# 5_SDRAM.net
KiCad netlist of a schematic drawn in Altium Designer
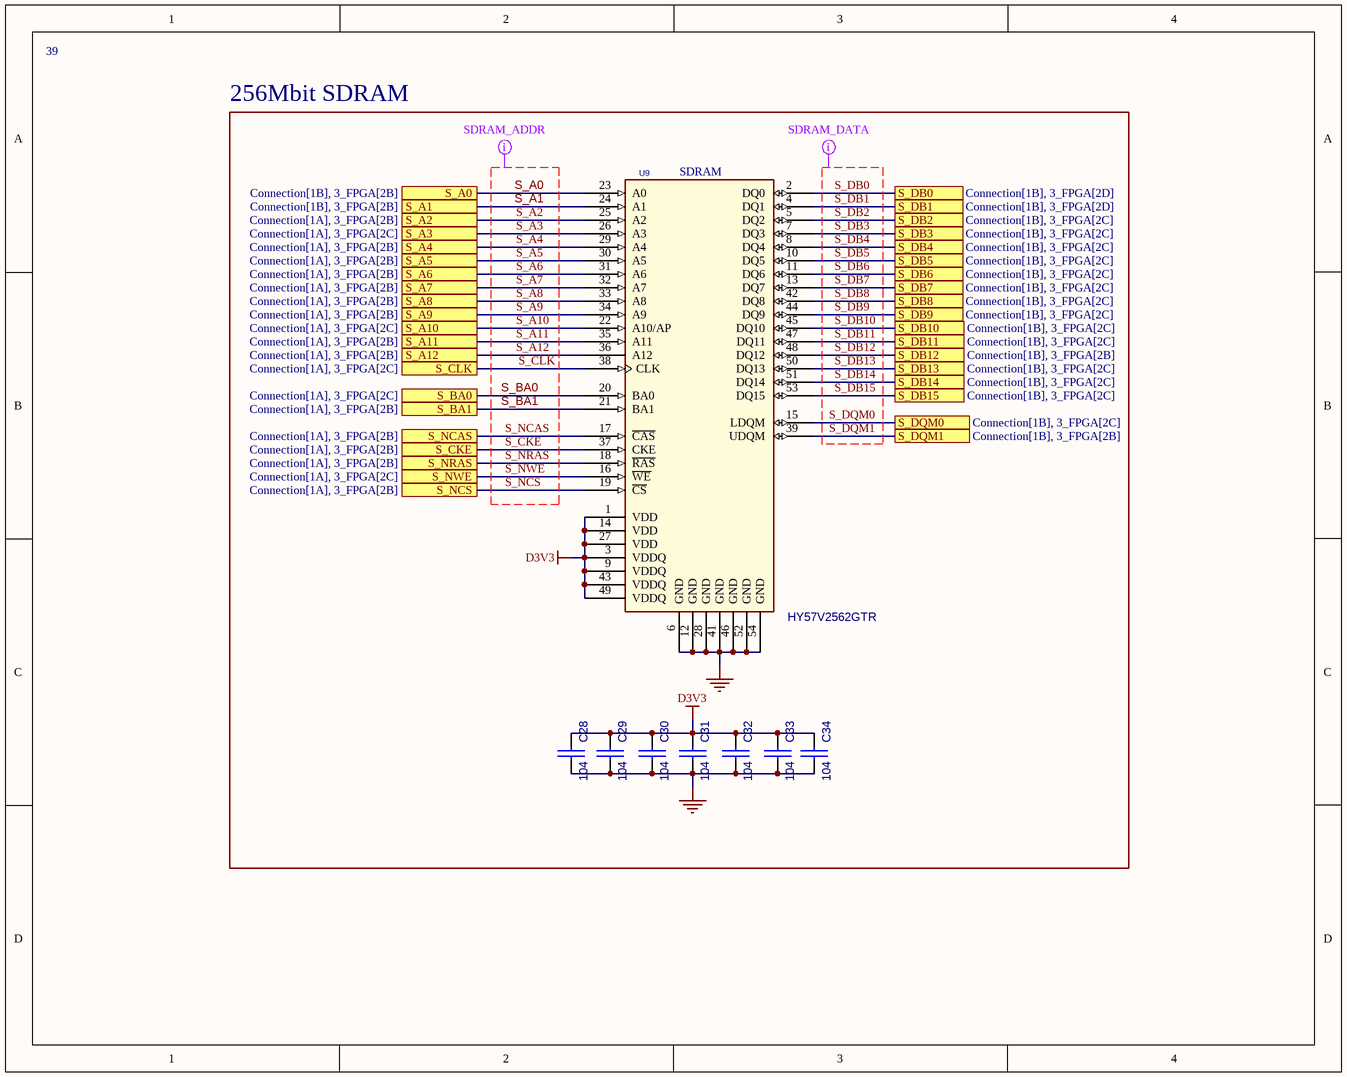
[diagram p0: 5_SDRAM.SchDoc]

(export (version "E")
  (design (tool "Eeschema 10.0.6"))
  (components
    (comp (ref "C28") (value "104") (footprint "0402 Cap") (libsource (lib "SPARTAN6") (part "C_Dup3")))
    (comp (ref "C29") (value "104") (footprint "0402 Cap") (libsource (lib "SPARTAN6") (part "C_Dup3")))
    (comp (ref "C30") (value "104") (footprint "0402 Cap") (libsource (lib "SPARTAN6") (part "C_Dup3")))
    (comp (ref "C31") (value "104") (footprint "0402 Cap") (libsource (lib "SPARTAN6") (part "C_Dup3")))
    (comp (ref "C32") (value "104") (footprint "0402 Cap") (libsource (lib "SPARTAN6") (part "C_Dup3")))
    (comp (ref "C33") (value "104") (footprint "0402 Cap") (libsource (lib "SPARTAN6") (part "C_Dup3")))
    (comp (ref "C34") (value "104") (footprint "0402 Cap") (libsource (lib "SPARTAN6") (part "C_Dup3")))
    (comp (ref "U9") (value "HY57V2562GTR") (libsource (lib "*") (part "HY57651620/SO_0")))
  )
  (nets
    (net (code "1") (name "/S_A0") (class "Default")
      (node (ref "U9") (pin "23") (pinfunction "A0_23") (pintype "input"))
    )
    (net (code "2") (name "/S_A1") (class "Default")
      (node (ref "U9") (pin "24") (pinfunction "A1_24") (pintype "input"))
    )
    (net (code "3") (name "/S_A2") (class "Default")
      (node (ref "U9") (pin "25") (pinfunction "A2_25") (pintype "input"))
    )
    (net (code "4") (name "/S_A3") (class "Default")
      (node (ref "U9") (pin "26") (pinfunction "A3_26") (pintype "input"))
    )
    (net (code "5") (name "/S_A4") (class "Default")
      (node (ref "U9") (pin "29") (pinfunction "A4_29") (pintype "input"))
    )
    (net (code "6") (name "/S_A5") (class "Default")
      (node (ref "U9") (pin "30") (pinfunction "A5_30") (pintype "input"))
    )
    (net (code "7") (name "/S_A6") (class "Default")
      (node (ref "U9") (pin "31") (pinfunction "A6_31") (pintype "input"))
    )
    (net (code "8") (name "/S_A7") (class "Default")
      (node (ref "U9") (pin "32") (pinfunction "A7_32") (pintype "input"))
    )
    (net (code "9") (name "/S_A8") (class "Default")
      (node (ref "U9") (pin "33") (pinfunction "A8_33") (pintype "input"))
    )
    (net (code "10") (name "/S_A9") (class "Default")
      (node (ref "U9") (pin "34") (pinfunction "A9_34") (pintype "input"))
    )
    (net (code "11") (name "/S_A10") (class "Default")
      (node (ref "U9") (pin "22") (pinfunction "A10/AP_22") (pintype "input"))
    )
    (net (code "12") (name "/S_A11") (class "Default")
      (node (ref "U9") (pin "35") (pinfunction "A11_35") (pintype "input"))
    )
    (net (code "13") (name "/S_A12") (class "Default")
      (node (ref "U9") (pin "36") (pinfunction "A12_36") (pintype "passive"))
    )
    (net (code "14") (name "/S_BA0") (class "Default")
      (node (ref "U9") (pin "20") (pinfunction "BA0_20") (pintype "input"))
    )
    (net (code "15") (name "/S_BA1") (class "Default")
      (node (ref "U9") (pin "21") (pinfunction "BA1_21") (pintype "input"))
    )
    (net (code "16") (name "/S_CKE") (class "Default")
      (node (ref "U9") (pin "37") (pinfunction "CKE_37") (pintype "input"))
    )
    (net (code "17") (name "/S_CLK") (class "Default")
      (node (ref "U9") (pin "38") (pinfunction "CLK_38") (pintype "input"))
    )
    (net (code "18") (name "/S_DB0") (class "Default")
      (node (ref "U9") (pin "2") (pinfunction "DQ0_2") (pintype "bidirectional"))
    )
    (net (code "19") (name "/S_DB1") (class "Default")
      (node (ref "U9") (pin "4") (pinfunction "DQ1_4") (pintype "bidirectional"))
    )
    (net (code "20") (name "/S_DB2") (class "Default")
      (node (ref "U9") (pin "5") (pinfunction "DQ2_5") (pintype "bidirectional"))
    )
    (net (code "21") (name "/S_DB3") (class "Default")
      (node (ref "U9") (pin "7") (pinfunction "DQ3_7") (pintype "bidirectional"))
    )
    (net (code "22") (name "/S_DB4") (class "Default")
      (node (ref "U9") (pin "8") (pinfunction "DQ4_8") (pintype "bidirectional"))
    )
    (net (code "23") (name "/S_DB5") (class "Default")
      (node (ref "U9") (pin "10") (pinfunction "DQ5_10") (pintype "bidirectional"))
    )
    (net (code "24") (name "/S_DB6") (class "Default")
      (node (ref "U9") (pin "11") (pinfunction "DQ6_11") (pintype "bidirectional"))
    )
    (net (code "25") (name "/S_DB7") (class "Default")
      (node (ref "U9") (pin "13") (pinfunction "DQ7_13") (pintype "bidirectional"))
    )
    (net (code "26") (name "/S_DB8") (class "Default")
      (node (ref "U9") (pin "42") (pinfunction "DQ8_42") (pintype "bidirectional"))
    )
    (net (code "27") (name "/S_DB9") (class "Default")
      (node (ref "U9") (pin "44") (pinfunction "DQ9_44") (pintype "bidirectional"))
    )
    (net (code "28") (name "/S_DB10") (class "Default")
      (node (ref "U9") (pin "45") (pinfunction "DQ10_45") (pintype "bidirectional"))
    )
    (net (code "29") (name "/S_DB11") (class "Default")
      (node (ref "U9") (pin "47") (pinfunction "DQ11_47") (pintype "bidirectional"))
    )
    (net (code "30") (name "/S_DB12") (class "Default")
      (node (ref "U9") (pin "48") (pinfunction "DQ12_48") (pintype "bidirectional"))
    )
    (net (code "31") (name "/S_DB13") (class "Default")
      (node (ref "U9") (pin "50") (pinfunction "DQ13_50") (pintype "bidirectional"))
    )
    (net (code "32") (name "/S_DB14") (class "Default")
      (node (ref "U9") (pin "51") (pinfunction "DQ14_51") (pintype "bidirectional"))
    )
    (net (code "33") (name "/S_DB15") (class "Default")
      (node (ref "U9") (pin "53") (pinfunction "DQ15_53") (pintype "bidirectional"))
    )
    (net (code "34") (name "/S_DQM0") (class "Default")
      (node (ref "U9") (pin "15") (pinfunction "LDQM_15") (pintype "bidirectional"))
    )
    (net (code "35") (name "/S_DQM1") (class "Default")
      (node (ref "U9") (pin "39") (pinfunction "UDQM_39") (pintype "bidirectional"))
    )
    (net (code "36") (name "/S_NCAS") (class "Default")
      (node (ref "U9") (pin "17") (pinfunction "~{CAS}_17") (pintype "input"))
    )
    (net (code "37") (name "/S_NCS") (class "Default")
      (node (ref "U9") (pin "19") (pinfunction "~{CS}_19") (pintype "input"))
    )
    (net (code "38") (name "/S_NRAS") (class "Default")
      (node (ref "U9") (pin "18") (pinfunction "~{RAS}_18") (pintype "input"))
    )
    (net (code "39") (name "/S_NWE") (class "Default")
      (node (ref "U9") (pin "16") (pinfunction "~{WE}_16") (pintype "input"))
    )
    (net (code "40") (name "D3V3") (class "Default")
      (node (ref "C28") (pin "1") (pinfunction "1_1") (pintype "passive"))
      (node (ref "C29") (pin "1") (pinfunction "1_1") (pintype "passive"))
      (node (ref "C30") (pin "1") (pinfunction "1_1") (pintype "passive"))
      (node (ref "C31") (pin "1") (pinfunction "1_1") (pintype "passive"))
      (node (ref "C32") (pin "1") (pinfunction "1_1") (pintype "passive"))
      (node (ref "C33") (pin "1") (pinfunction "1_1") (pintype "passive"))
      (node (ref "C34") (pin "1") (pinfunction "1_1") (pintype "passive"))
      (node (ref "U9") (pin "1") (pinfunction "VDD_1") (pintype "power_in"))
      (node (ref "U9") (pin "14") (pinfunction "VDD_14") (pintype "power_in"))
      (node (ref "U9") (pin "27") (pinfunction "VDD_27") (pintype "power_in"))
      (node (ref "U9") (pin "3") (pinfunction "VDDQ_3") (pintype "power_in"))
      (node (ref "U9") (pin "43") (pinfunction "VDDQ_43") (pintype "power_in"))
      (node (ref "U9") (pin "49") (pinfunction "VDDQ_49") (pintype "power_in"))
      (node (ref "U9") (pin "9") (pinfunction "VDDQ_9") (pintype "power_in"))
    )
    (net (code "41") (name "GND") (class "Default")
      (node (ref "C28") (pin "2") (pinfunction "2_2") (pintype "passive"))
      (node (ref "C29") (pin "2") (pinfunction "2_2") (pintype "passive"))
      (node (ref "C30") (pin "2") (pinfunction "2_2") (pintype "passive"))
      (node (ref "C31") (pin "2") (pinfunction "2_2") (pintype "passive"))
      (node (ref "C32") (pin "2") (pinfunction "2_2") (pintype "passive"))
      (node (ref "C33") (pin "2") (pinfunction "2_2") (pintype "passive"))
      (node (ref "C34") (pin "2") (pinfunction "2_2") (pintype "passive"))
      (node (ref "U9") (pin "12") (pinfunction "GND_12") (pintype "power_in"))
      (node (ref "U9") (pin "28") (pinfunction "GND_28") (pintype "power_in"))
      (node (ref "U9") (pin "41") (pinfunction "GND_41") (pintype "power_in"))
      (node (ref "U9") (pin "46") (pinfunction "GND_46") (pintype "power_in"))
      (node (ref "U9") (pin "52") (pinfunction "GND_52") (pintype "power_in"))
      (node (ref "U9") (pin "54") (pinfunction "GND_54") (pintype "power_in"))
      (node (ref "U9") (pin "6") (pinfunction "GND_6") (pintype "power_in"))
    )
  )
)
